# WiFi_DAC.net
KiCad netlist of a schematic drawn in EAGLE
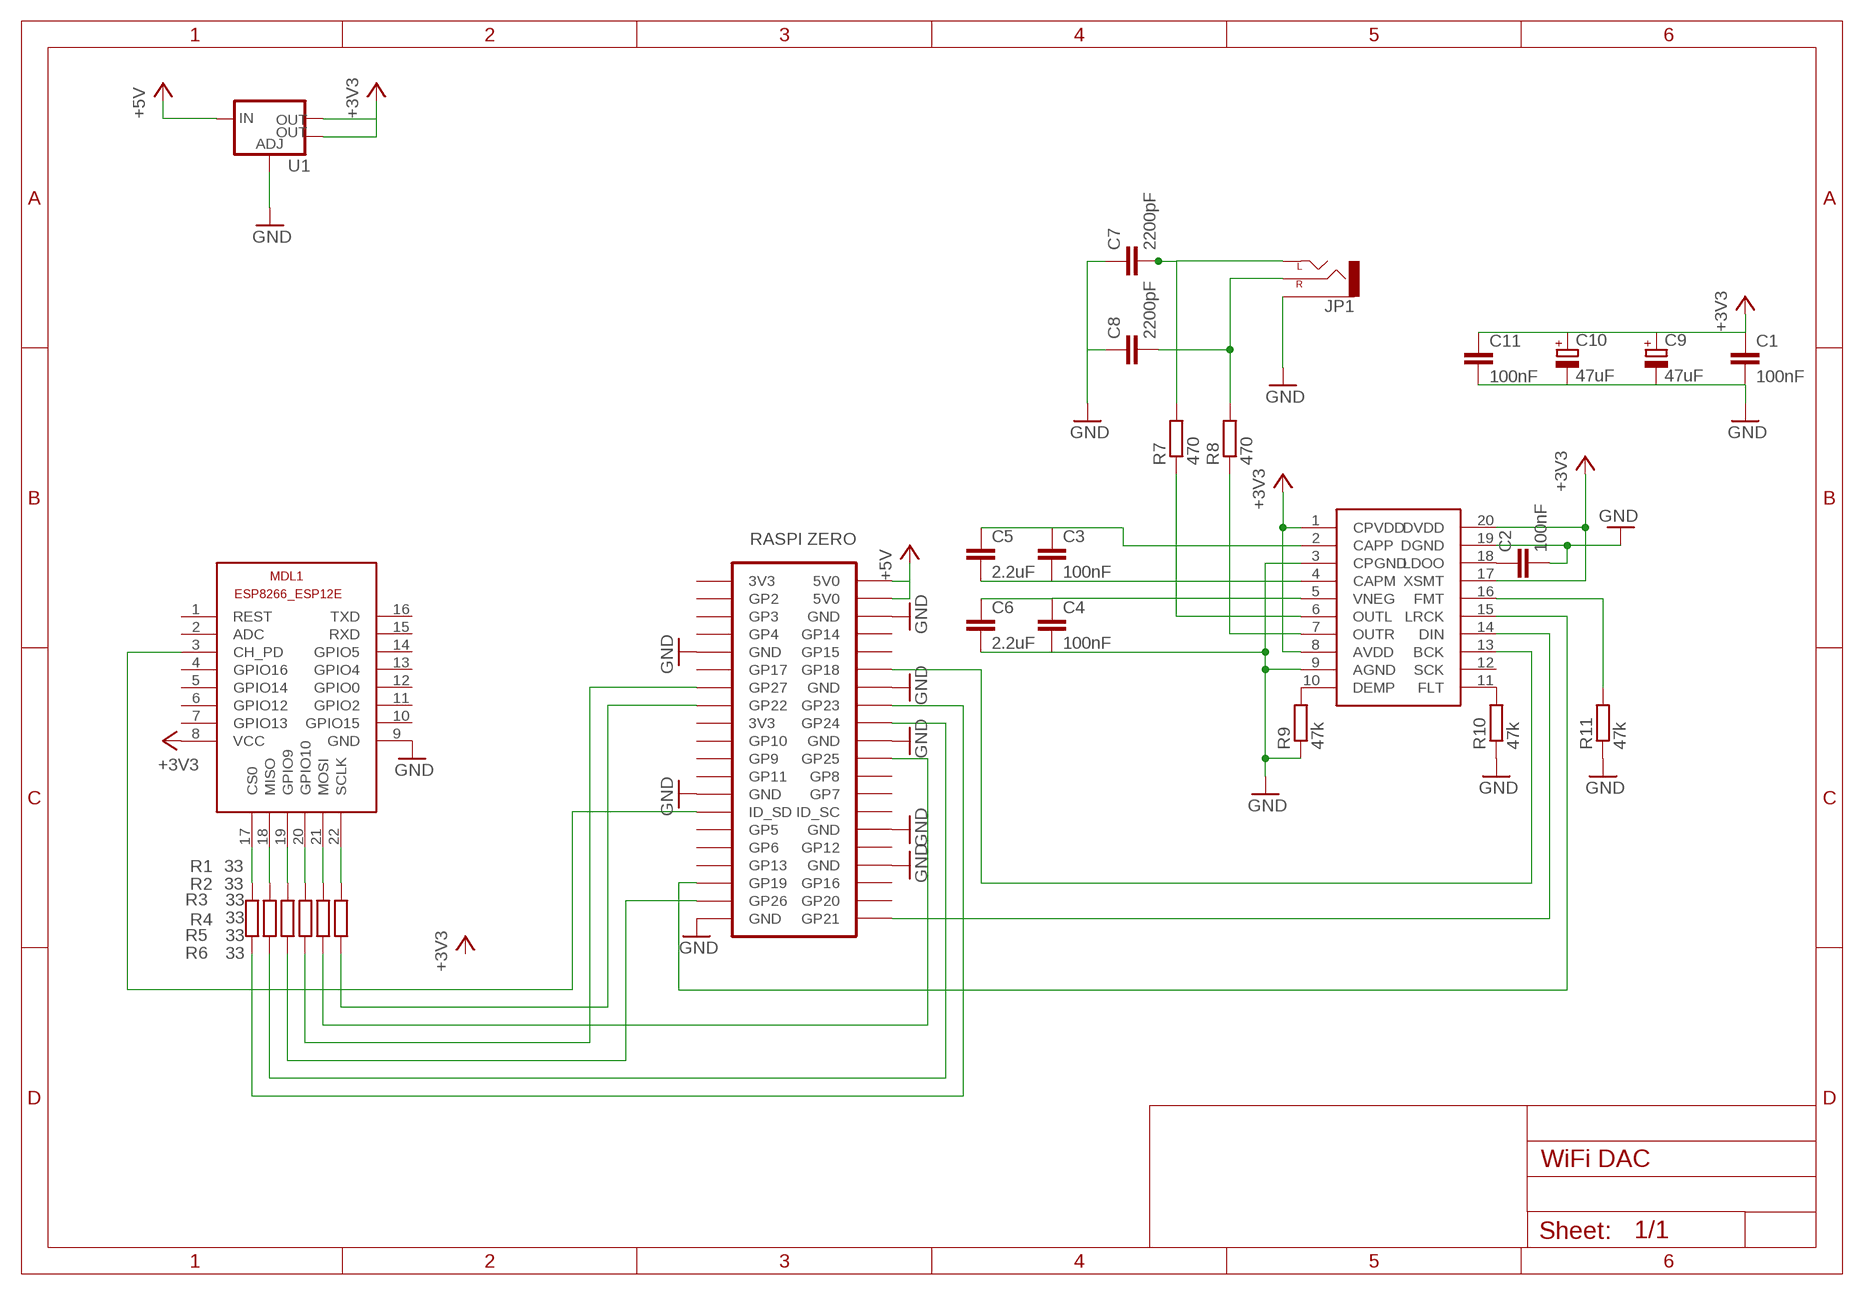
[diagram p0: schematic, sheet 1]

(export (version "E")
  (design (tool "Eeschema 10.0.6"))
  (components
    (comp (ref "C1")
      (value "100nF")
      (footprint "eagle-import:C0603")
      (libsource (lib "eagle-import") (part "C-EUC0603"))
    )
    (comp (ref "C2")
      (value "100nF")
      (footprint "eagle-import:C0603")
      (libsource (lib "eagle-import") (part "C-EUC0603"))
    )
    (comp (ref "C3")
      (value "100nF")
      (footprint "eagle-import:C0603")
      (libsource (lib "eagle-import") (part "C-EUC0603"))
    )
    (comp (ref "C4")
      (value "100nF")
      (footprint "eagle-import:C0603")
      (libsource (lib "eagle-import") (part "C-EUC0603"))
    )
    (comp (ref "C5")
      (value "2.2uF")
      (footprint "eagle-import:C0603")
      (libsource (lib "eagle-import") (part "C-EUC0603"))
    )
    (comp (ref "C6")
      (value "2.2uF")
      (footprint "eagle-import:C0603")
      (libsource (lib "eagle-import") (part "C-EUC0603"))
    )
    (comp (ref "C7")
      (value "2200pF")
      (footprint "eagle-import:C0603")
      (libsource (lib "eagle-import") (part "C-EUC0603"))
    )
    (comp (ref "C8")
      (value "2200pF")
      (footprint "eagle-import:C0603")
      (libsource (lib "eagle-import") (part "C-EUC0603"))
    )
    (comp (ref "C9")
      (value "47uF")
      (footprint "eagle-import:SANYO-OSCON_SMD_A5")
      (libsource (lib "eagle-import") (part "CPOL-EUSANYO_SMD_A5"))
    )
    (comp (ref "C10")
      (value "47uF")
      (footprint "eagle-import:SANYO-OSCON_SMD_A5")
      (libsource (lib "eagle-import") (part "CPOL-EUSANYO_SMD_A5"))
    )
    (comp (ref "C11")
      (value "100nF")
      (footprint "eagle-import:C0603")
      (libsource (lib "eagle-import") (part "C-EUC0603"))
    )
    (comp (ref "JP1")
      (value "AUDIO-JACKPTH")
      (footprint "eagle-import:AUDIO-JACK")
      (libsource (lib "eagle-import") (part "AUDIO-JACKPTH"))
    )
    (comp (ref "MDL1")
      (value "ESP8266-12EESP8266-ESP12E")
      (footprint "eagle-import:ESP8266-ESP12E")
      (libsource (lib "eagle-import") (part "ESP8266-12EESP8266-ESP12E"))
    )
    (comp (ref "R1")
      (value "33")
      (footprint "eagle-import:R0603")
      (libsource (lib "eagle-import") (part "R-EU_R0603"))
    )
    (comp (ref "R2")
      (value "33")
      (footprint "eagle-import:R0603")
      (libsource (lib "eagle-import") (part "R-EU_R0603"))
    )
    (comp (ref "R3")
      (value "33")
      (footprint "eagle-import:R0603")
      (libsource (lib "eagle-import") (part "R-EU_R0603"))
    )
    (comp (ref "R4")
      (value "33")
      (footprint "eagle-import:R0603")
      (libsource (lib "eagle-import") (part "R-EU_R0603"))
    )
    (comp (ref "R5")
      (value "33")
      (footprint "eagle-import:R0603")
      (libsource (lib "eagle-import") (part "R-EU_R0603"))
    )
    (comp (ref "R6")
      (value "33")
      (footprint "eagle-import:R0603")
      (libsource (lib "eagle-import") (part "R-EU_R0603"))
    )
    (comp (ref "R7")
      (value "470")
      (footprint "eagle-import:R0603")
      (libsource (lib "eagle-import") (part "R-EU_R0603"))
    )
    (comp (ref "R8")
      (value "470")
      (footprint "eagle-import:R0603")
      (libsource (lib "eagle-import") (part "R-EU_R0603"))
    )
    (comp (ref "R9")
      (value "47k")
      (footprint "eagle-import:R0603")
      (libsource (lib "eagle-import") (part "R-EU_R0603"))
    )
    (comp (ref "R10")
      (value "47k")
      (footprint "eagle-import:R0603")
      (libsource (lib "eagle-import") (part "R-EU_R0603"))
    )
    (comp (ref "R11")
      (value "47k")
      (footprint "eagle-import:R0603")
      (libsource (lib "eagle-import") (part "R-EU_R0603"))
    )
    (comp (ref "U$1")
      (value "ZERO")
      (footprint "eagle-import:ZERO")
      (libsource (lib "eagle-import") (part "ZERO"))
    )
    (comp (ref "U$2")
      (value "PCM5102")
      (footprint "eagle-import:TSSOP20")
      (libsource (lib "eagle-import") (part "PCM5102"))
    )
    (comp (ref "U1")
      (value "V_REG_LM1117SOT223")
      (footprint "eagle-import:SOT223")
      (libsource (lib "eagle-import") (part "V_REG_LM1117SOT223"))
    )
  )
  (nets
    (net (code "1") (name "+3V3") (class "Default")
      (node (ref "C1") (pin "1") (pinfunction "1_1") (pintype "passive"))
      (node (ref "C10") (pin "+") (pinfunction "+_+") (pintype "passive"))
      (node (ref "C11") (pin "1") (pinfunction "1_1") (pintype "passive"))
      (node (ref "C9") (pin "+") (pinfunction "+_+") (pintype "passive"))
      (node (ref "MDL1") (pin "8") (pinfunction "VCC_8") (pintype "bidirectional"))
      (node (ref "U$2") (pin "1") (pinfunction "CPVDD_1") (pintype "bidirectional"))
      (node (ref "U$2") (pin "17") (pinfunction "XSMT_17") (pintype "bidirectional"))
      (node (ref "U$2") (pin "20") (pinfunction "DVDD_20") (pintype "bidirectional"))
      (node (ref "U$2") (pin "8") (pinfunction "AVDD_8") (pintype "bidirectional"))
      (node (ref "U1") (pin "2") (pinfunction "OUT_2") (pintype "output"))
      (node (ref "U1") (pin "4") (pinfunction "OUT_4") (pintype "output"))
    )
    (net (code "2") (name "+5V") (class "Default")
      (node (ref "U$1") (pin "2") (pinfunction "5V0_2") (pintype "bidirectional"))
      (node (ref "U$1") (pin "4") (pinfunction "5V0_4") (pintype "bidirectional"))
      (node (ref "U1") (pin "3") (pinfunction "IN_3") (pintype "input"))
    )
    (net (code "3") (name "GND") (class "Default")
      (node (ref "C1") (pin "2") (pinfunction "2_2") (pintype "passive"))
      (node (ref "C10") (pin "-") (pinfunction "-_-") (pintype "passive"))
      (node (ref "C11") (pin "2") (pinfunction "2_2") (pintype "passive"))
      (node (ref "C2") (pin "2") (pinfunction "2_2") (pintype "passive"))
      (node (ref "C4") (pin "2") (pinfunction "2_2") (pintype "passive"))
      (node (ref "C6") (pin "2") (pinfunction "2_2") (pintype "passive"))
      (node (ref "C7") (pin "1") (pinfunction "1_1") (pintype "passive"))
      (node (ref "C8") (pin "1") (pinfunction "1_1") (pintype "passive"))
      (node (ref "C9") (pin "-") (pinfunction "-_-") (pintype "passive"))
      (node (ref "JP1") (pin "SLEEVE") (pinfunction "SLEEVE_SLEEVE") (pintype "bidirectional"))
      (node (ref "MDL1") (pin "9") (pinfunction "GND_9") (pintype "bidirectional"))
      (node (ref "R10") (pin "1") (pinfunction "1_1") (pintype "passive"))
      (node (ref "R11") (pin "1") (pinfunction "1_1") (pintype "passive"))
      (node (ref "R9") (pin "1") (pinfunction "1_1") (pintype "passive"))
      (node (ref "U$1") (pin "14") (pinfunction "GND_14") (pintype "bidirectional"))
      (node (ref "U$1") (pin "20") (pinfunction "GND_20") (pintype "bidirectional"))
      (node (ref "U$1") (pin "25") (pinfunction "GND_25") (pintype "bidirectional"))
      (node (ref "U$1") (pin "30") (pinfunction "GND_30") (pintype "bidirectional"))
      (node (ref "U$1") (pin "34") (pinfunction "GND_34") (pintype "bidirectional"))
      (node (ref "U$1") (pin "39") (pinfunction "GND_39") (pintype "bidirectional"))
      (node (ref "U$1") (pin "6") (pinfunction "GND_6") (pintype "bidirectional"))
      (node (ref "U$1") (pin "9") (pinfunction "GND_9") (pintype "bidirectional"))
      (node (ref "U$2") (pin "19") (pinfunction "DGND_19") (pintype "bidirectional"))
      (node (ref "U$2") (pin "3") (pinfunction "CPGND_3") (pintype "bidirectional"))
      (node (ref "U$2") (pin "9") (pinfunction "AGND_9") (pintype "bidirectional"))
      (node (ref "U1") (pin "1") (pinfunction "ADJ_1") (pintype "input"))
    )
    (net (code "4") (name "Net-(JP1-LEFT)") (class "Default")
      (node (ref "C7") (pin "2") (pinfunction "2_2") (pintype "passive"))
      (node (ref "JP1") (pin "TIP") (pinfunction "LEFT_TIP") (pintype "bidirectional"))
      (node (ref "R7") (pin "2") (pinfunction "2_2") (pintype "passive"))
    )
    (net (code "5") (name "Net-(JP1-RIGHT)") (class "Default")
      (node (ref "C8") (pin "2") (pinfunction "2_2") (pintype "passive"))
      (node (ref "JP1") (pin "RING") (pinfunction "RIGHT_RING") (pintype "bidirectional"))
      (node (ref "R8") (pin "2") (pinfunction "2_2") (pintype "passive"))
    )
    (net (code "6") (name "Net-(MDL1-CH_PD)") (class "Default")
      (node (ref "MDL1") (pin "3") (pinfunction "CH_PD_3") (pintype "bidirectional"))
      (node (ref "U$1") (pin "27") (pinfunction "ID_SD_27") (pintype "bidirectional"))
    )
    (net (code "7") (name "Net-(MDL1-CS0)") (class "Default")
      (node (ref "MDL1") (pin "17") (pinfunction "CS0_17") (pintype "bidirectional"))
      (node (ref "R1") (pin "2") (pinfunction "2_2") (pintype "passive"))
    )
    (net (code "8") (name "Net-(MDL1-GPIO9)") (class "Default")
      (node (ref "MDL1") (pin "19") (pinfunction "GPIO9_19") (pintype "bidirectional"))
      (node (ref "R3") (pin "2") (pinfunction "2_2") (pintype "passive"))
    )
    (net (code "9") (name "Net-(MDL1-GPIO10)") (class "Default")
      (node (ref "MDL1") (pin "20") (pinfunction "GPIO10_20") (pintype "bidirectional"))
      (node (ref "R4") (pin "2") (pinfunction "2_2") (pintype "passive"))
    )
    (net (code "10") (name "Net-(MDL1-MISO)") (class "Default")
      (node (ref "MDL1") (pin "18") (pinfunction "MISO_18") (pintype "bidirectional"))
      (node (ref "R2") (pin "2") (pinfunction "2_2") (pintype "passive"))
    )
    (net (code "11") (name "Net-(MDL1-MOSI)") (class "Default")
      (node (ref "MDL1") (pin "21") (pinfunction "MOSI_21") (pintype "bidirectional"))
      (node (ref "R5") (pin "2") (pinfunction "2_2") (pintype "passive"))
    )
    (net (code "12") (name "Net-(MDL1-SCLK)") (class "Default")
      (node (ref "MDL1") (pin "22") (pinfunction "SCLK_22") (pintype "bidirectional"))
      (node (ref "R6") (pin "2") (pinfunction "2_2") (pintype "passive"))
    )
    (net (code "13") (name "Net-(U$1-GP18)") (class "Default")
      (node (ref "U$1") (pin "12") (pinfunction "GP18_12") (pintype "bidirectional"))
      (node (ref "U$2") (pin "13") (pinfunction "BCK_13") (pintype "bidirectional"))
    )
    (net (code "14") (name "Net-(U$1-GP19)") (class "Default")
      (node (ref "U$1") (pin "35") (pinfunction "GP19_35") (pintype "bidirectional"))
      (node (ref "U$2") (pin "15") (pinfunction "LRCK_15") (pintype "bidirectional"))
    )
    (net (code "15") (name "Net-(U$1-GP21)") (class "Default")
      (node (ref "U$1") (pin "40") (pinfunction "GP21_40") (pintype "bidirectional"))
      (node (ref "U$2") (pin "14") (pinfunction "DIN_14") (pintype "bidirectional"))
    )
    (net (code "16") (name "Net-(U$1-GP22)") (class "Default")
      (node (ref "R6") (pin "1") (pinfunction "1_1") (pintype "passive"))
      (node (ref "U$1") (pin "15") (pinfunction "GP22_15") (pintype "bidirectional"))
    )
    (net (code "17") (name "Net-(U$1-GP23)") (class "Default")
      (node (ref "R1") (pin "1") (pinfunction "1_1") (pintype "passive"))
      (node (ref "U$1") (pin "16") (pinfunction "GP23_16") (pintype "bidirectional"))
    )
    (net (code "18") (name "Net-(U$1-GP24)") (class "Default")
      (node (ref "R2") (pin "1") (pinfunction "1_1") (pintype "passive"))
      (node (ref "U$1") (pin "18") (pinfunction "GP24_18") (pintype "bidirectional"))
    )
    (net (code "19") (name "Net-(U$1-GP25)") (class "Default")
      (node (ref "R5") (pin "1") (pinfunction "1_1") (pintype "passive"))
      (node (ref "U$1") (pin "22") (pinfunction "GP25_22") (pintype "bidirectional"))
    )
    (net (code "20") (name "Net-(U$1-GP26)") (class "Default")
      (node (ref "R3") (pin "1") (pinfunction "1_1") (pintype "passive"))
      (node (ref "U$1") (pin "37") (pinfunction "GP26_37") (pintype "bidirectional"))
    )
    (net (code "21") (name "Net-(U$1-GP27)") (class "Default")
      (node (ref "R4") (pin "1") (pinfunction "1_1") (pintype "passive"))
      (node (ref "U$1") (pin "13") (pinfunction "GP27_13") (pintype "bidirectional"))
    )
    (net (code "22") (name "Net-(U$2-CAPM)") (class "Default")
      (node (ref "C3") (pin "2") (pinfunction "2_2") (pintype "passive"))
      (node (ref "C5") (pin "2") (pinfunction "2_2") (pintype "passive"))
      (node (ref "U$2") (pin "4") (pinfunction "CAPM_4") (pintype "bidirectional"))
    )
    (net (code "23") (name "Net-(U$2-CAPP)") (class "Default")
      (node (ref "C3") (pin "1") (pinfunction "1_1") (pintype "passive"))
      (node (ref "C5") (pin "1") (pinfunction "1_1") (pintype "passive"))
      (node (ref "U$2") (pin "2") (pinfunction "CAPP_2") (pintype "bidirectional"))
    )
    (net (code "24") (name "Net-(U$2-DEMP)") (class "Default")
      (node (ref "R9") (pin "2") (pinfunction "2_2") (pintype "passive"))
      (node (ref "U$2") (pin "10") (pinfunction "DEMP_10") (pintype "bidirectional"))
    )
    (net (code "25") (name "Net-(U$2-FLT)") (class "Default")
      (node (ref "R10") (pin "2") (pinfunction "2_2") (pintype "passive"))
      (node (ref "U$2") (pin "11") (pinfunction "FLT_11") (pintype "bidirectional"))
    )
    (net (code "26") (name "Net-(U$2-FMT)") (class "Default")
      (node (ref "R11") (pin "2") (pinfunction "2_2") (pintype "passive"))
      (node (ref "U$2") (pin "16") (pinfunction "FMT_16") (pintype "bidirectional"))
    )
    (net (code "27") (name "Net-(U$2-LDOO)") (class "Default")
      (node (ref "C2") (pin "1") (pinfunction "1_1") (pintype "passive"))
      (node (ref "U$2") (pin "18") (pinfunction "LDOO_18") (pintype "bidirectional"))
    )
    (net (code "28") (name "Net-(U$2-OUTL)") (class "Default")
      (node (ref "R7") (pin "1") (pinfunction "1_1") (pintype "passive"))
      (node (ref "U$2") (pin "6") (pinfunction "OUTL_6") (pintype "bidirectional"))
    )
    (net (code "29") (name "Net-(U$2-OUTR)") (class "Default")
      (node (ref "R8") (pin "1") (pinfunction "1_1") (pintype "passive"))
      (node (ref "U$2") (pin "7") (pinfunction "OUTR_7") (pintype "bidirectional"))
    )
    (net (code "30") (name "Net-(U$2-VNEG)") (class "Default")
      (node (ref "C4") (pin "1") (pinfunction "1_1") (pintype "passive"))
      (node (ref "C6") (pin "1") (pinfunction "1_1") (pintype "passive"))
      (node (ref "U$2") (pin "5") (pinfunction "VNEG_5") (pintype "bidirectional"))
    )
    (net (code "31") (name "unconnected-(MDL1-ADC-Pad2)") (class "Default")
      (node (ref "MDL1") (pin "2") (pinfunction "ADC_2") (pintype "bidirectional"))
    )
    (net (code "32") (name "unconnected-(MDL1-GPIO0-Pad12)") (class "Default")
      (node (ref "MDL1") (pin "12") (pinfunction "GPIO0_12") (pintype "bidirectional"))
    )
    (net (code "33") (name "unconnected-(MDL1-GPIO2-Pad11)") (class "Default")
      (node (ref "MDL1") (pin "11") (pinfunction "GPIO2_11") (pintype "bidirectional"))
    )
    (net (code "34") (name "unconnected-(MDL1-GPIO4-Pad13)") (class "Default")
      (node (ref "MDL1") (pin "13") (pinfunction "GPIO4_13") (pintype "bidirectional"))
    )
    (net (code "35") (name "unconnected-(MDL1-GPIO5-Pad14)") (class "Default")
      (node (ref "MDL1") (pin "14") (pinfunction "GPIO5_14") (pintype "bidirectional"))
    )
    (net (code "36") (name "unconnected-(MDL1-GPIO12-Pad6)") (class "Default")
      (node (ref "MDL1") (pin "6") (pinfunction "GPIO12_6") (pintype "bidirectional"))
    )
    (net (code "37") (name "unconnected-(MDL1-GPIO13-Pad7)") (class "Default")
      (node (ref "MDL1") (pin "7") (pinfunction "GPIO13_7") (pintype "bidirectional"))
    )
    (net (code "38") (name "unconnected-(MDL1-GPIO14-Pad5)") (class "Default")
      (node (ref "MDL1") (pin "5") (pinfunction "GPIO14_5") (pintype "bidirectional"))
    )
    (net (code "39") (name "unconnected-(MDL1-GPIO15-Pad10)") (class "Default")
      (node (ref "MDL1") (pin "10") (pinfunction "GPIO15_10") (pintype "bidirectional"))
    )
    (net (code "40") (name "unconnected-(MDL1-GPIO16-Pad4)") (class "Default")
      (node (ref "MDL1") (pin "4") (pinfunction "GPIO16_4") (pintype "bidirectional"))
    )
    (net (code "41") (name "unconnected-(MDL1-REST-Pad1)") (class "Default")
      (node (ref "MDL1") (pin "1") (pinfunction "REST_1") (pintype "bidirectional"))
    )
    (net (code "42") (name "unconnected-(MDL1-RXD-Pad15)") (class "Default")
      (node (ref "MDL1") (pin "15") (pinfunction "RXD_15") (pintype "bidirectional"))
    )
    (net (code "43") (name "unconnected-(MDL1-TXD-Pad16)") (class "Default")
      (node (ref "MDL1") (pin "16") (pinfunction "TXD_16") (pintype "bidirectional"))
    )
    (net (code "44") (name "unconnected-(U$1-3V3-Pad1)") (class "Default")
      (node (ref "U$1") (pin "1") (pinfunction "3V3_1") (pintype "bidirectional"))
    )
    (net (code "45") (name "unconnected-(U$1-3V3-Pad17)") (class "Default")
      (node (ref "U$1") (pin "17") (pinfunction "3V3_17") (pintype "bidirectional"))
    )
    (net (code "46") (name "unconnected-(U$1-GP2-Pad3)") (class "Default")
      (node (ref "U$1") (pin "3") (pinfunction "GP2_3") (pintype "bidirectional"))
    )
    (net (code "47") (name "unconnected-(U$1-GP3-Pad5)") (class "Default")
      (node (ref "U$1") (pin "5") (pinfunction "GP3_5") (pintype "bidirectional"))
    )
    (net (code "48") (name "unconnected-(U$1-GP4-Pad7)") (class "Default")
      (node (ref "U$1") (pin "7") (pinfunction "GP4_7") (pintype "bidirectional"))
    )
    (net (code "49") (name "unconnected-(U$1-GP5-Pad29)") (class "Default")
      (node (ref "U$1") (pin "29") (pinfunction "GP5_29") (pintype "bidirectional"))
    )
    (net (code "50") (name "unconnected-(U$1-GP6-Pad31)") (class "Default")
      (node (ref "U$1") (pin "31") (pinfunction "GP6_31") (pintype "bidirectional"))
    )
    (net (code "51") (name "unconnected-(U$1-GP7-Pad26)") (class "Default")
      (node (ref "U$1") (pin "26") (pinfunction "GP7_26") (pintype "bidirectional"))
    )
    (net (code "52") (name "unconnected-(U$1-GP8-Pad24)") (class "Default")
      (node (ref "U$1") (pin "24") (pinfunction "GP8_24") (pintype "bidirectional"))
    )
    (net (code "53") (name "unconnected-(U$1-GP9-Pad21)") (class "Default")
      (node (ref "U$1") (pin "21") (pinfunction "GP9_21") (pintype "bidirectional"))
    )
    (net (code "54") (name "unconnected-(U$1-GP10-Pad19)") (class "Default")
      (node (ref "U$1") (pin "19") (pinfunction "GP10_19") (pintype "bidirectional"))
    )
    (net (code "55") (name "unconnected-(U$1-GP11-Pad23)") (class "Default")
      (node (ref "U$1") (pin "23") (pinfunction "GP11_23") (pintype "bidirectional"))
    )
    (net (code "56") (name "unconnected-(U$1-GP12-Pad32)") (class "Default")
      (node (ref "U$1") (pin "32") (pinfunction "GP12_32") (pintype "bidirectional"))
    )
    (net (code "57") (name "unconnected-(U$1-GP13-Pad33)") (class "Default")
      (node (ref "U$1") (pin "33") (pinfunction "GP13_33") (pintype "bidirectional"))
    )
    (net (code "58") (name "unconnected-(U$1-GP14-Pad8)") (class "Default")
      (node (ref "U$1") (pin "8") (pinfunction "GP14_8") (pintype "bidirectional"))
    )
    (net (code "59") (name "unconnected-(U$1-GP15-Pad10)") (class "Default")
      (node (ref "U$1") (pin "10") (pinfunction "GP15_10") (pintype "bidirectional"))
    )
    (net (code "60") (name "unconnected-(U$1-GP16-Pad36)") (class "Default")
      (node (ref "U$1") (pin "36") (pinfunction "GP16_36") (pintype "bidirectional"))
    )
    (net (code "61") (name "unconnected-(U$1-GP17-Pad11)") (class "Default")
      (node (ref "U$1") (pin "11") (pinfunction "GP17_11") (pintype "bidirectional"))
    )
    (net (code "62") (name "unconnected-(U$1-GP20-Pad38)") (class "Default")
      (node (ref "U$1") (pin "38") (pinfunction "GP20_38") (pintype "bidirectional"))
    )
    (net (code "63") (name "unconnected-(U$1-ID_SC-Pad28)") (class "Default")
      (node (ref "U$1") (pin "28") (pinfunction "ID_SC_28") (pintype "bidirectional"))
    )
    (net (code "64") (name "unconnected-(U$2-SCK-Pad12)") (class "Default")
      (node (ref "U$2") (pin "12") (pinfunction "SCK_12") (pintype "bidirectional"))
    )
  )
)
